# alt_sche.net
KiCad netlist of a schematic drawn in Altium Designer
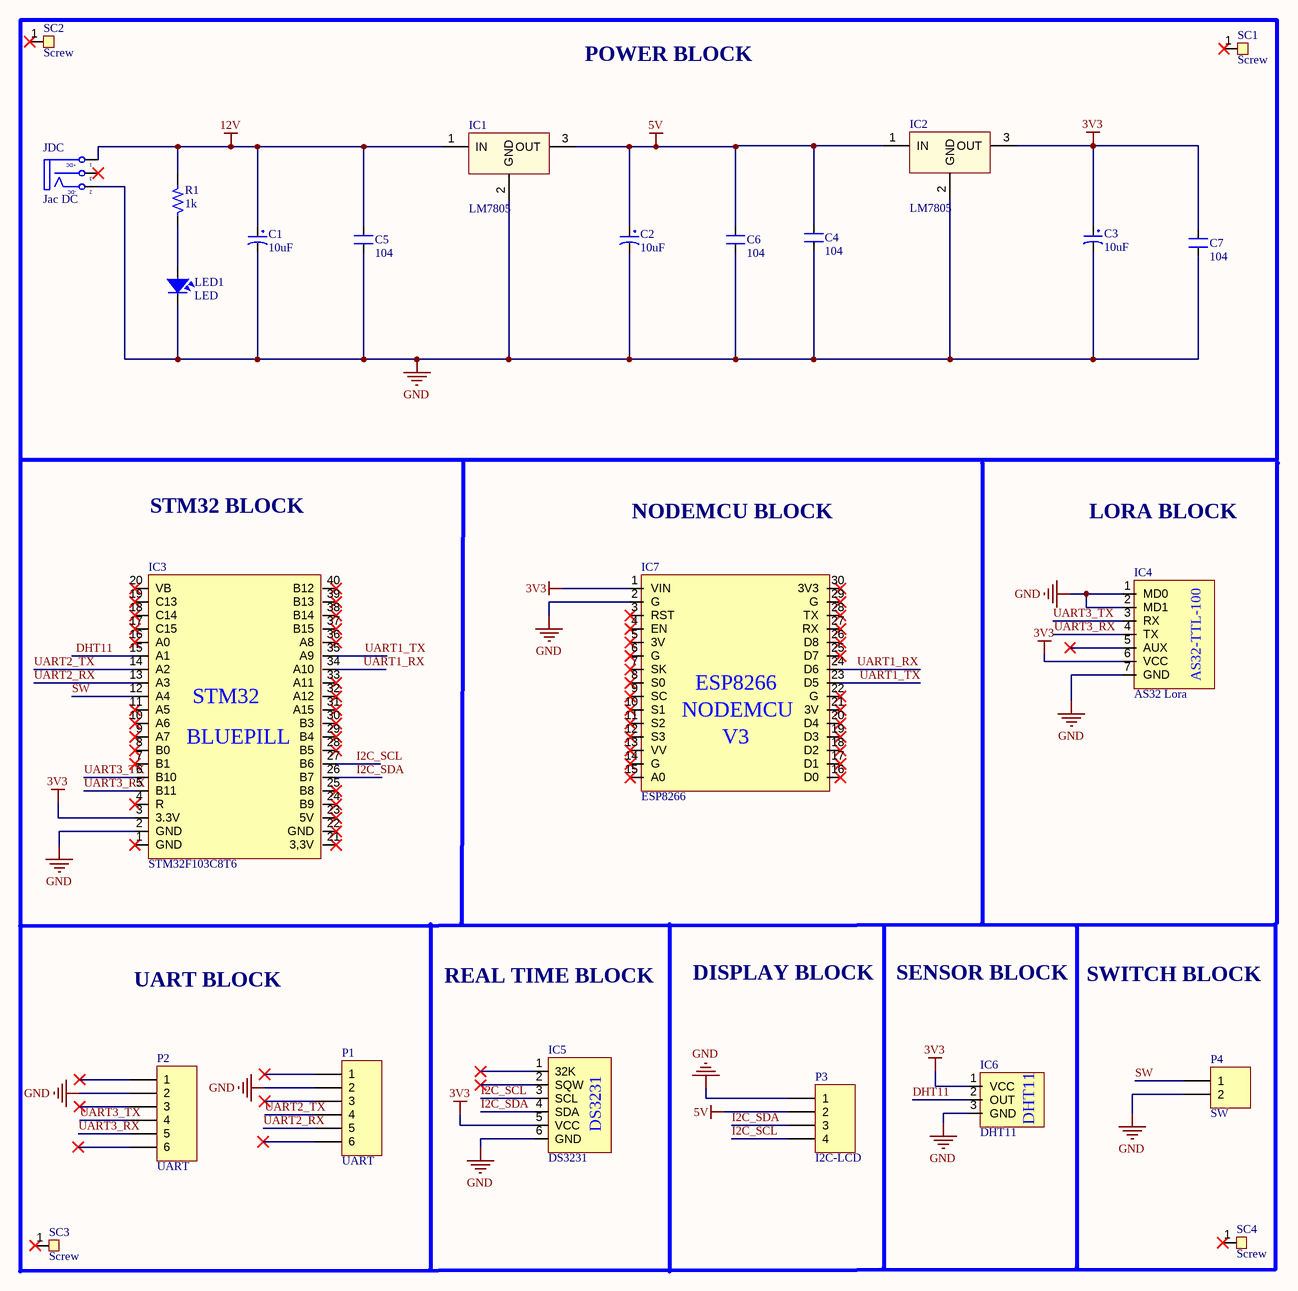
[diagram p0: alt_sche.SchDoc]

(export (version "E")
  (design (tool "Eeschema 10.0.6"))
  (components
    (comp (ref "C1")
      (value "10uF")
      (footprint "CP1/2")
      (description "Cap P  0,1uF < 22uF , 16 - 50V")
      (libsource (lib "syhaunguyen") (part "CP1"))
    )
    (comp (ref "C2")
      (value "10uF")
      (footprint "CP1/2")
      (description "Cap P  0,1uF < 22uF , 16 - 50V")
      (libsource (lib "syhaunguyen") (part "CP1"))
    )
    (comp (ref "C3")
      (value "10uF")
      (footprint "CP1/2")
      (description "Cap P  0,1uF < 22uF , 16 - 50V")
      (libsource (lib "syhaunguyen") (part "CP1"))
    )
    (comp (ref "C4")
      (value "104")
      (footprint "CN2")
      (description "Cap np 104 => 105pF")
      (libsource (lib "syhaunguyen") (part "CN2"))
    )
    (comp (ref "C5")
      (value "104")
      (footprint "CN2")
      (description "Cap np 104 => 105pF")
      (libsource (lib "syhaunguyen") (part "CN2"))
    )
    (comp (ref "C6")
      (value "104")
      (footprint "CN2")
      (description "Cap np 104 => 105pF")
      (libsource (lib "syhaunguyen") (part "CN2"))
    )
    (comp (ref "C7")
      (value "104")
      (footprint "CN2")
      (description "Cap np 104 => 105pF")
      (libsource (lib "syhaunguyen") (part "CN2"))
    )
    (comp (ref "IC1")
      (value "LM7805")
      (footprint "QTO-220")
      (description "On ap +, from + 5 to + 24VDC")
      (libsource (lib "syhaunguyen") (part "LM78xx"))
    )
    (comp (ref "IC2")
      (value "LM7805")
      (footprint "QTO-220")
      (description "On ap +, from + 5 to + 24VDC")
      (libsource (lib "syhaunguyen") (part "LM78xx"))
    )
    (comp (ref "IC3")
      (value "STM32F103C8T6")
      (footprint "STM32_BLUEPILL")
      (libsource (lib "Lib_Inter") (part "STM32_BLUEPILL"))
    )
    (comp (ref "IC4") (value "AS32 Lora") (footprint "LORA") (libsource (lib "Lib_Inter") (part "LORA")))
    (comp (ref "IC5") (value "DS3231") (footprint "DS3231") (libsource (lib "Lib_Inter") (part "DS3231")))
    (comp (ref "IC6") (value "DHT11") (footprint "DHT11") (libsource (lib "Lib_Inter") (part "DHT11")))
    (comp (ref "IC7") (value "ESP8266") (footprint "ESP8266") (libsource (lib "Lib_Inter") (part "ESP8266")))
    (comp (ref "JDC")
      (value "Jac DC")
      (footprint "DC-IN")
      (description "Jac DC input")
      (libsource (lib "syhaunguyen") (part "DCIN"))
    )
    (comp (ref "LED1")
      (value "LED")
      (footprint "LED-3")
      (description "LED Single colour Green and Red")
      (libsource (lib "syhaunguyen") (part "LED"))
    )
    (comp (ref "P1")
      (value "UART")
      (footprint "HDR1X6")
      (description "Header, 6-Pin")
      (fields (field (name "PUBLISHER") "Altium Limited"))
      (libsource (lib "Library AL") (part "Header 6"))
    )
    (comp (ref "P2")
      (value "UART")
      (footprint "HDR1X6")
      (description "Header, 6-Pin")
      (fields (field (name "PUBLISHER") "Altium Limited"))
      (libsource (lib "Library AL") (part "Header 6"))
    )
    (comp (ref "P3")
      (value "I2C-LCD")
      (footprint "HDR1X4")
      (description "Header, 4-Pin")
      (fields (field (name "PUBLISHER") "Altium Limited"))
      (libsource (lib "Library AL") (part "Header 4"))
    )
    (comp (ref "P4")
      (value "SW")
      (footprint "HDR1X2")
      (description "Header, 2-Pin")
      (fields (field (name "PUBLISHER") "Altium Limited"))
      (libsource (lib "Library AL") (part "Header 2"))
    )
    (comp (ref "R1")
      (value "1k")
      (footprint "R1/4W")
      (description "Resistor 1/4W")
      (libsource (lib "syhaunguyen") (part "R"))
    )
    (comp (ref "SC1")
      (value "Screw")
      (footprint "Screw 3 small")
      (libsource (lib "duc_libra") (part "screw 3 small"))
    )
    (comp (ref "SC2")
      (value "Screw")
      (footprint "Screw 3 small")
      (libsource (lib "duc_libra") (part "screw 3 small"))
    )
    (comp (ref "SC3")
      (value "Screw")
      (footprint "Screw 3 small")
      (libsource (lib "duc_libra") (part "screw 3 small"))
    )
    (comp (ref "SC4")
      (value "Screw")
      (footprint "Screw 3 small")
      (libsource (lib "duc_libra") (part "screw 3 small"))
    )
  )
  (nets
    (net (code "1") (name "/DHT11") (class "Default")
      (node (ref "IC3") (pin "15") (pinfunction "A1_15") (pintype "passive"))
      (node (ref "IC6") (pin "2") (pinfunction "OUT_2") (pintype "passive"))
    )
    (net (code "2") (name "/I2C_SCL") (class "Default")
      (node (ref "IC3") (pin "27") (pinfunction "B6_27") (pintype "passive"))
      (node (ref "IC5") (pin "3") (pinfunction "SCL_3") (pintype "passive"))
      (node (ref "P3") (pin "4") (pinfunction "4_4") (pintype "passive"))
    )
    (net (code "3") (name "/I2C_SDA") (class "Default")
      (node (ref "IC3") (pin "26") (pinfunction "B7_26") (pintype "passive"))
      (node (ref "IC5") (pin "4") (pinfunction "SDA_4") (pintype "passive"))
      (node (ref "P3") (pin "3") (pinfunction "3_3") (pintype "passive"))
    )
    (net (code "4") (name "/SW") (class "Default")
      (node (ref "IC3") (pin "12") (pinfunction "A4_12") (pintype "passive"))
      (node (ref "P4") (pin "1") (pinfunction "1_1") (pintype "passive"))
    )
    (net (code "5") (name "/UART1_RX") (class "Default")
      (node (ref "IC3") (pin "34") (pinfunction "A10_34") (pintype "passive"))
      (node (ref "IC7") (pin "24") (pinfunction "D6_24") (pintype "passive"))
    )
    (net (code "6") (name "/UART1_TX") (class "Default")
      (node (ref "IC3") (pin "35") (pinfunction "A9_35") (pintype "passive"))
      (node (ref "IC7") (pin "23") (pinfunction "D5_23") (pintype "passive"))
    )
    (net (code "7") (name "/UART2_RX") (class "Default")
      (node (ref "IC3") (pin "13") (pinfunction "A3_13") (pintype "passive"))
      (node (ref "P1") (pin "5") (pinfunction "5_5") (pintype "passive"))
    )
    (net (code "8") (name "/UART2_TX") (class "Default")
      (node (ref "IC3") (pin "14") (pinfunction "A2_14") (pintype "passive"))
      (node (ref "P1") (pin "4") (pinfunction "4_4") (pintype "passive"))
    )
    (net (code "9") (name "/UART3_RX") (class "Default")
      (node (ref "IC3") (pin "5") (pinfunction "B11_5") (pintype "passive"))
      (node (ref "IC4") (pin "4") (pinfunction "TX_4") (pintype "passive"))
      (node (ref "P2") (pin "5") (pinfunction "5_5") (pintype "passive"))
    )
    (net (code "10") (name "/UART3_TX") (class "Default")
      (node (ref "IC3") (pin "6") (pinfunction "B10_6") (pintype "passive"))
      (node (ref "IC4") (pin "3") (pinfunction "RX_3") (pintype "passive"))
      (node (ref "P2") (pin "4") (pinfunction "4_4") (pintype "passive"))
    )
    (net (code "11") (name "3V3") (class "Default")
      (node (ref "C3") (pin "1") (pinfunction "1_1") (pintype "passive"))
      (node (ref "C7") (pin "2") (pinfunction "2_2") (pintype "passive"))
      (node (ref "IC2") (pin "3") (pinfunction "OUT_3") (pintype "passive"))
      (node (ref "IC3") (pin "3") (pinfunction "3.3V_3") (pintype "passive"))
      (node (ref "IC4") (pin "6") (pinfunction "VCC_6") (pintype "passive"))
      (node (ref "IC5") (pin "5") (pinfunction "VCC_5") (pintype "passive"))
      (node (ref "IC6") (pin "1") (pinfunction "VCC_1") (pintype "passive"))
      (node (ref "IC7") (pin "1") (pinfunction "VIN_1") (pintype "passive"))
    )
    (net (code "12") (name "5V") (class "Default")
      (node (ref "C2") (pin "1") (pinfunction "1_1") (pintype "passive"))
      (node (ref "C4") (pin "2") (pinfunction "2_2") (pintype "passive"))
      (node (ref "C6") (pin "2") (pinfunction "2_2") (pintype "passive"))
      (node (ref "IC1") (pin "3") (pinfunction "OUT_3") (pintype "passive"))
      (node (ref "IC2") (pin "1") (pinfunction "IN_1") (pintype "passive"))
      (node (ref "P3") (pin "2") (pinfunction "2_2") (pintype "passive"))
    )
    (net (code "13") (name "12V") (class "Default")
      (node (ref "C1") (pin "1") (pinfunction "1_1") (pintype "passive"))
      (node (ref "C5") (pin "2") (pinfunction "2_2") (pintype "passive"))
      (node (ref "IC1") (pin "1") (pinfunction "IN_1") (pintype "passive"))
      (node (ref "JDC") (pin "1") (pinfunction "T_1") (pintype "passive"))
      (node (ref "R1") (pin "2") (pinfunction "2_2") (pintype "passive"))
    )
    (net (code "14") (name "GND") (class "Default")
      (node (ref "C1") (pin "2") (pinfunction "2_2") (pintype "passive"))
      (node (ref "C2") (pin "2") (pinfunction "2_2") (pintype "passive"))
      (node (ref "C3") (pin "2") (pinfunction "2_2") (pintype "passive"))
      (node (ref "C4") (pin "1") (pinfunction "1_1") (pintype "passive"))
      (node (ref "C5") (pin "1") (pinfunction "1_1") (pintype "passive"))
      (node (ref "C6") (pin "1") (pinfunction "1_1") (pintype "passive"))
      (node (ref "C7") (pin "1") (pinfunction "1_1") (pintype "passive"))
      (node (ref "IC1") (pin "2") (pinfunction "GND_2") (pintype "passive"))
      (node (ref "IC2") (pin "2") (pinfunction "GND_2") (pintype "passive"))
      (node (ref "IC3") (pin "2") (pinfunction "GND_2") (pintype "passive"))
      (node (ref "IC4") (pin "1") (pinfunction "MD0_1") (pintype "passive"))
      (node (ref "IC4") (pin "2") (pinfunction "MD1_2") (pintype "passive"))
      (node (ref "IC4") (pin "7") (pinfunction "GND_7") (pintype "passive"))
      (node (ref "IC5") (pin "6") (pinfunction "GND_6") (pintype "passive"))
      (node (ref "IC6") (pin "3") (pinfunction "GND_3") (pintype "passive"))
      (node (ref "IC7") (pin "2") (pinfunction "G_2") (pintype "passive"))
      (node (ref "JDC") (pin "2") (pinfunction "TN_2") (pintype "passive"))
      (node (ref "LED1") (pin "2") (pinfunction "2_2") (pintype "passive"))
      (node (ref "P1") (pin "2") (pinfunction "2_2") (pintype "passive"))
      (node (ref "P2") (pin "2") (pinfunction "2_2") (pintype "passive"))
      (node (ref "P3") (pin "1") (pinfunction "1_1") (pintype "passive"))
      (node (ref "P4") (pin "2") (pinfunction "2_2") (pintype "passive"))
    )
    (net (code "15") (name "Net-(LED1-Pad1)") (class "Default")
      (node (ref "LED1") (pin "1") (pinfunction "1_1") (pintype "passive"))
      (node (ref "R1") (pin "1") (pinfunction "1_1") (pintype "passive"))
    )
    (net (code "16") (name "unconnected-(IC3-3,3V-Pad21)") (class "Default")
      (node (ref "IC3") (pin "21") (pinfunction "3,3V_21") (pintype "passive+no_connect"))
    )
    (net (code "17") (name "unconnected-(IC3-5V-Pad23)") (class "Default")
      (node (ref "IC3") (pin "23") (pinfunction "5V_23") (pintype "passive+no_connect"))
    )
    (net (code "18") (name "unconnected-(IC3-A0-Pad16)") (class "Default")
      (node (ref "IC3") (pin "16") (pinfunction "A0_16") (pintype "passive+no_connect"))
    )
    (net (code "19") (name "unconnected-(IC3-A5-Pad11)") (class "Default")
      (node (ref "IC3") (pin "11") (pinfunction "A5_11") (pintype "passive+no_connect"))
    )
    (net (code "20") (name "unconnected-(IC3-A6-Pad10)") (class "Default")
      (node (ref "IC3") (pin "10") (pinfunction "A6_10") (pintype "passive+no_connect"))
    )
    (net (code "21") (name "unconnected-(IC3-A7-Pad9)") (class "Default")
      (node (ref "IC3") (pin "9") (pinfunction "A7_9") (pintype "passive+no_connect"))
    )
    (net (code "22") (name "unconnected-(IC3-A8-Pad36)") (class "Default")
      (node (ref "IC3") (pin "36") (pinfunction "A8_36") (pintype "passive+no_connect"))
    )
    (net (code "23") (name "unconnected-(IC3-A11-Pad33)") (class "Default")
      (node (ref "IC3") (pin "33") (pinfunction "A11_33") (pintype "passive+no_connect"))
    )
    (net (code "24") (name "unconnected-(IC3-A12-Pad32)") (class "Default")
      (node (ref "IC3") (pin "32") (pinfunction "A12_32") (pintype "passive+no_connect"))
    )
    (net (code "25") (name "unconnected-(IC3-A15-Pad31)") (class "Default")
      (node (ref "IC3") (pin "31") (pinfunction "A15_31") (pintype "passive+no_connect"))
    )
    (net (code "26") (name "unconnected-(IC3-B0-Pad8)") (class "Default")
      (node (ref "IC3") (pin "8") (pinfunction "B0_8") (pintype "passive+no_connect"))
    )
    (net (code "27") (name "unconnected-(IC3-B1-Pad7)") (class "Default")
      (node (ref "IC3") (pin "7") (pinfunction "B1_7") (pintype "passive+no_connect"))
    )
    (net (code "28") (name "unconnected-(IC3-B3-Pad30)") (class "Default")
      (node (ref "IC3") (pin "30") (pinfunction "B3_30") (pintype "passive+no_connect"))
    )
    (net (code "29") (name "unconnected-(IC3-B4-Pad29)") (class "Default")
      (node (ref "IC3") (pin "29") (pinfunction "B4_29") (pintype "passive+no_connect"))
    )
    (net (code "30") (name "unconnected-(IC3-B5-Pad28)") (class "Default")
      (node (ref "IC3") (pin "28") (pinfunction "B5_28") (pintype "passive+no_connect"))
    )
    (net (code "31") (name "unconnected-(IC3-B8-Pad25)") (class "Default")
      (node (ref "IC3") (pin "25") (pinfunction "B8_25") (pintype "passive+no_connect"))
    )
    (net (code "32") (name "unconnected-(IC3-B9-Pad24)") (class "Default")
      (node (ref "IC3") (pin "24") (pinfunction "B9_24") (pintype "passive+no_connect"))
    )
    (net (code "33") (name "unconnected-(IC3-B12-Pad40)") (class "Default")
      (node (ref "IC3") (pin "40") (pinfunction "B12_40") (pintype "passive+no_connect"))
    )
    (net (code "34") (name "unconnected-(IC3-B13-Pad39)") (class "Default")
      (node (ref "IC3") (pin "39") (pinfunction "B13_39") (pintype "passive+no_connect"))
    )
    (net (code "35") (name "unconnected-(IC3-B14-Pad38)") (class "Default")
      (node (ref "IC3") (pin "38") (pinfunction "B14_38") (pintype "passive+no_connect"))
    )
    (net (code "36") (name "unconnected-(IC3-B15-Pad37)") (class "Default")
      (node (ref "IC3") (pin "37") (pinfunction "B15_37") (pintype "passive+no_connect"))
    )
    (net (code "37") (name "unconnected-(IC3-C13-Pad19)") (class "Default")
      (node (ref "IC3") (pin "19") (pinfunction "C13_19") (pintype "passive+no_connect"))
    )
    (net (code "38") (name "unconnected-(IC3-C14-Pad18)") (class "Default")
      (node (ref "IC3") (pin "18") (pinfunction "C14_18") (pintype "passive+no_connect"))
    )
    (net (code "39") (name "unconnected-(IC3-C15-Pad17)") (class "Default")
      (node (ref "IC3") (pin "17") (pinfunction "C15_17") (pintype "passive+no_connect"))
    )
    (net (code "40") (name "unconnected-(IC3-GND-Pad1)") (class "Default")
      (node (ref "IC3") (pin "1") (pinfunction "GND_1") (pintype "passive+no_connect"))
    )
    (net (code "41") (name "unconnected-(IC3-GND-Pad22)") (class "Default")
      (node (ref "IC3") (pin "22") (pinfunction "GND_22") (pintype "passive+no_connect"))
    )
    (net (code "42") (name "unconnected-(IC3-R-Pad4)") (class "Default")
      (node (ref "IC3") (pin "4") (pinfunction "R_4") (pintype "passive+no_connect"))
    )
    (net (code "43") (name "unconnected-(IC3-VB-Pad20)") (class "Default")
      (node (ref "IC3") (pin "20") (pinfunction "VB_20") (pintype "passive+no_connect"))
    )
    (net (code "44") (name "unconnected-(IC4-AUX-Pad5)") (class "Default")
      (node (ref "IC4") (pin "5") (pinfunction "AUX_5") (pintype "passive+no_connect"))
    )
    (net (code "45") (name "unconnected-(IC5-32K-Pad1)") (class "Default")
      (node (ref "IC5") (pin "1") (pinfunction "32K_1") (pintype "passive+no_connect"))
    )
    (net (code "46") (name "unconnected-(IC5-SQW-Pad2)") (class "Default")
      (node (ref "IC5") (pin "2") (pinfunction "SQW_2") (pintype "passive+no_connect"))
    )
    (net (code "47") (name "unconnected-(IC7-3V-Pad5)") (class "Default")
      (node (ref "IC7") (pin "5") (pinfunction "3V_5") (pintype "passive+no_connect"))
    )
    (net (code "48") (name "unconnected-(IC7-3V-Pad21)") (class "Default")
      (node (ref "IC7") (pin "21") (pinfunction "3V_21") (pintype "passive+no_connect"))
    )
    (net (code "49") (name "unconnected-(IC7-3V3-Pad30)") (class "Default")
      (node (ref "IC7") (pin "30") (pinfunction "3V3_30") (pintype "passive+no_connect"))
    )
    (net (code "50") (name "unconnected-(IC7-A0-Pad15)") (class "Default")
      (node (ref "IC7") (pin "15") (pinfunction "A0_15") (pintype "passive+no_connect"))
    )
    (net (code "51") (name "unconnected-(IC7-D0-Pad16)") (class "Default")
      (node (ref "IC7") (pin "16") (pinfunction "D0_16") (pintype "passive+no_connect"))
    )
    (net (code "52") (name "unconnected-(IC7-D1-Pad17)") (class "Default")
      (node (ref "IC7") (pin "17") (pinfunction "D1_17") (pintype "passive+no_connect"))
    )
    (net (code "53") (name "unconnected-(IC7-D2-Pad18)") (class "Default")
      (node (ref "IC7") (pin "18") (pinfunction "D2_18") (pintype "passive+no_connect"))
    )
    (net (code "54") (name "unconnected-(IC7-D3-Pad19)") (class "Default")
      (node (ref "IC7") (pin "19") (pinfunction "D3_19") (pintype "passive+no_connect"))
    )
    (net (code "55") (name "unconnected-(IC7-D4-Pad20)") (class "Default")
      (node (ref "IC7") (pin "20") (pinfunction "D4_20") (pintype "passive+no_connect"))
    )
    (net (code "56") (name "unconnected-(IC7-D7-Pad25)") (class "Default")
      (node (ref "IC7") (pin "25") (pinfunction "D7_25") (pintype "passive+no_connect"))
    )
    (net (code "57") (name "unconnected-(IC7-D8-Pad26)") (class "Default")
      (node (ref "IC7") (pin "26") (pinfunction "D8_26") (pintype "passive+no_connect"))
    )
    (net (code "58") (name "unconnected-(IC7-EN-Pad4)") (class "Default")
      (node (ref "IC7") (pin "4") (pinfunction "EN_4") (pintype "passive+no_connect"))
    )
    (net (code "59") (name "unconnected-(IC7-G-Pad6)") (class "Default")
      (node (ref "IC7") (pin "6") (pinfunction "G_6") (pintype "passive+no_connect"))
    )
    (net (code "60") (name "unconnected-(IC7-G-Pad14)") (class "Default")
      (node (ref "IC7") (pin "14") (pinfunction "G_14") (pintype "passive+no_connect"))
    )
    (net (code "61") (name "unconnected-(IC7-G-Pad22)") (class "Default")
      (node (ref "IC7") (pin "22") (pinfunction "G_22") (pintype "passive+no_connect"))
    )
    (net (code "62") (name "unconnected-(IC7-G-Pad29)") (class "Default")
      (node (ref "IC7") (pin "29") (pinfunction "G_29") (pintype "passive+no_connect"))
    )
    (net (code "63") (name "unconnected-(IC7-RST-Pad3)") (class "Default")
      (node (ref "IC7") (pin "3") (pinfunction "RST_3") (pintype "passive+no_connect"))
    )
    (net (code "64") (name "unconnected-(IC7-RX-Pad27)") (class "Default")
      (node (ref "IC7") (pin "27") (pinfunction "RX_27") (pintype "passive+no_connect"))
    )
    (net (code "65") (name "unconnected-(IC7-S0-Pad8)") (class "Default")
      (node (ref "IC7") (pin "8") (pinfunction "S0_8") (pintype "passive+no_connect"))
    )
    (net (code "66") (name "unconnected-(IC7-S1-Pad10)") (class "Default")
      (node (ref "IC7") (pin "10") (pinfunction "S1_10") (pintype "passive+no_connect"))
    )
    (net (code "67") (name "unconnected-(IC7-S2-Pad11)") (class "Default")
      (node (ref "IC7") (pin "11") (pinfunction "S2_11") (pintype "passive+no_connect"))
    )
    (net (code "68") (name "unconnected-(IC7-S3-Pad12)") (class "Default")
      (node (ref "IC7") (pin "12") (pinfunction "S3_12") (pintype "passive+no_connect"))
    )
    (net (code "69") (name "unconnected-(IC7-SC-Pad9)") (class "Default")
      (node (ref "IC7") (pin "9") (pinfunction "SC_9") (pintype "passive+no_connect"))
    )
    (net (code "70") (name "unconnected-(IC7-SK-Pad7)") (class "Default")
      (node (ref "IC7") (pin "7") (pinfunction "SK_7") (pintype "passive+no_connect"))
    )
    (net (code "71") (name "unconnected-(IC7-TX-Pad28)") (class "Default")
      (node (ref "IC7") (pin "28") (pinfunction "TX_28") (pintype "passive+no_connect"))
    )
    (net (code "72") (name "unconnected-(IC7-VV-Pad13)") (class "Default")
      (node (ref "IC7") (pin "13") (pinfunction "VV_13") (pintype "passive+no_connect"))
    )
    (net (code "73") (name "unconnected-(JDC-S-Pad3)") (class "Default")
      (node (ref "JDC") (pin "3") (pinfunction "S_3") (pintype "power_in+no_connect"))
    )
    (net (code "74") (name "unconnected-(P1-Pad1)") (class "Default")
      (node (ref "P1") (pin "1") (pinfunction "1_1") (pintype "passive+no_connect"))
    )
    (net (code "75") (name "unconnected-(P1-Pad3)") (class "Default")
      (node (ref "P1") (pin "3") (pinfunction "3_3") (pintype "passive+no_connect"))
    )
    (net (code "76") (name "unconnected-(P1-Pad6)") (class "Default")
      (node (ref "P1") (pin "6") (pinfunction "6_6") (pintype "passive+no_connect"))
    )
    (net (code "77") (name "unconnected-(P2-Pad1)") (class "Default")
      (node (ref "P2") (pin "1") (pinfunction "1_1") (pintype "passive+no_connect"))
    )
    (net (code "78") (name "unconnected-(P2-Pad3)") (class "Default")
      (node (ref "P2") (pin "3") (pinfunction "3_3") (pintype "passive+no_connect"))
    )
    (net (code "79") (name "unconnected-(P2-Pad6)") (class "Default")
      (node (ref "P2") (pin "6") (pinfunction "6_6") (pintype "passive+no_connect"))
    )
    (net (code "80") (name "unconnected-(SC1-Pad1)") (class "Default")
      (node (ref "SC1") (pin "1") (pinfunction "1_1") (pintype "passive+no_connect"))
    )
    (net (code "81") (name "unconnected-(SC2-Pad1)") (class "Default")
      (node (ref "SC2") (pin "1") (pinfunction "1_1") (pintype "passive+no_connect"))
    )
    (net (code "82") (name "unconnected-(SC3-Pad1)") (class "Default")
      (node (ref "SC3") (pin "1") (pinfunction "1_1") (pintype "passive+no_connect"))
    )
    (net (code "83") (name "unconnected-(SC4-Pad1)") (class "Default")
      (node (ref "SC4") (pin "1") (pinfunction "1_1") (pintype "passive+no_connect"))
    )
  )
)
